# Powersupply.net
KiCad netlist of a schematic drawn in Altium Designer
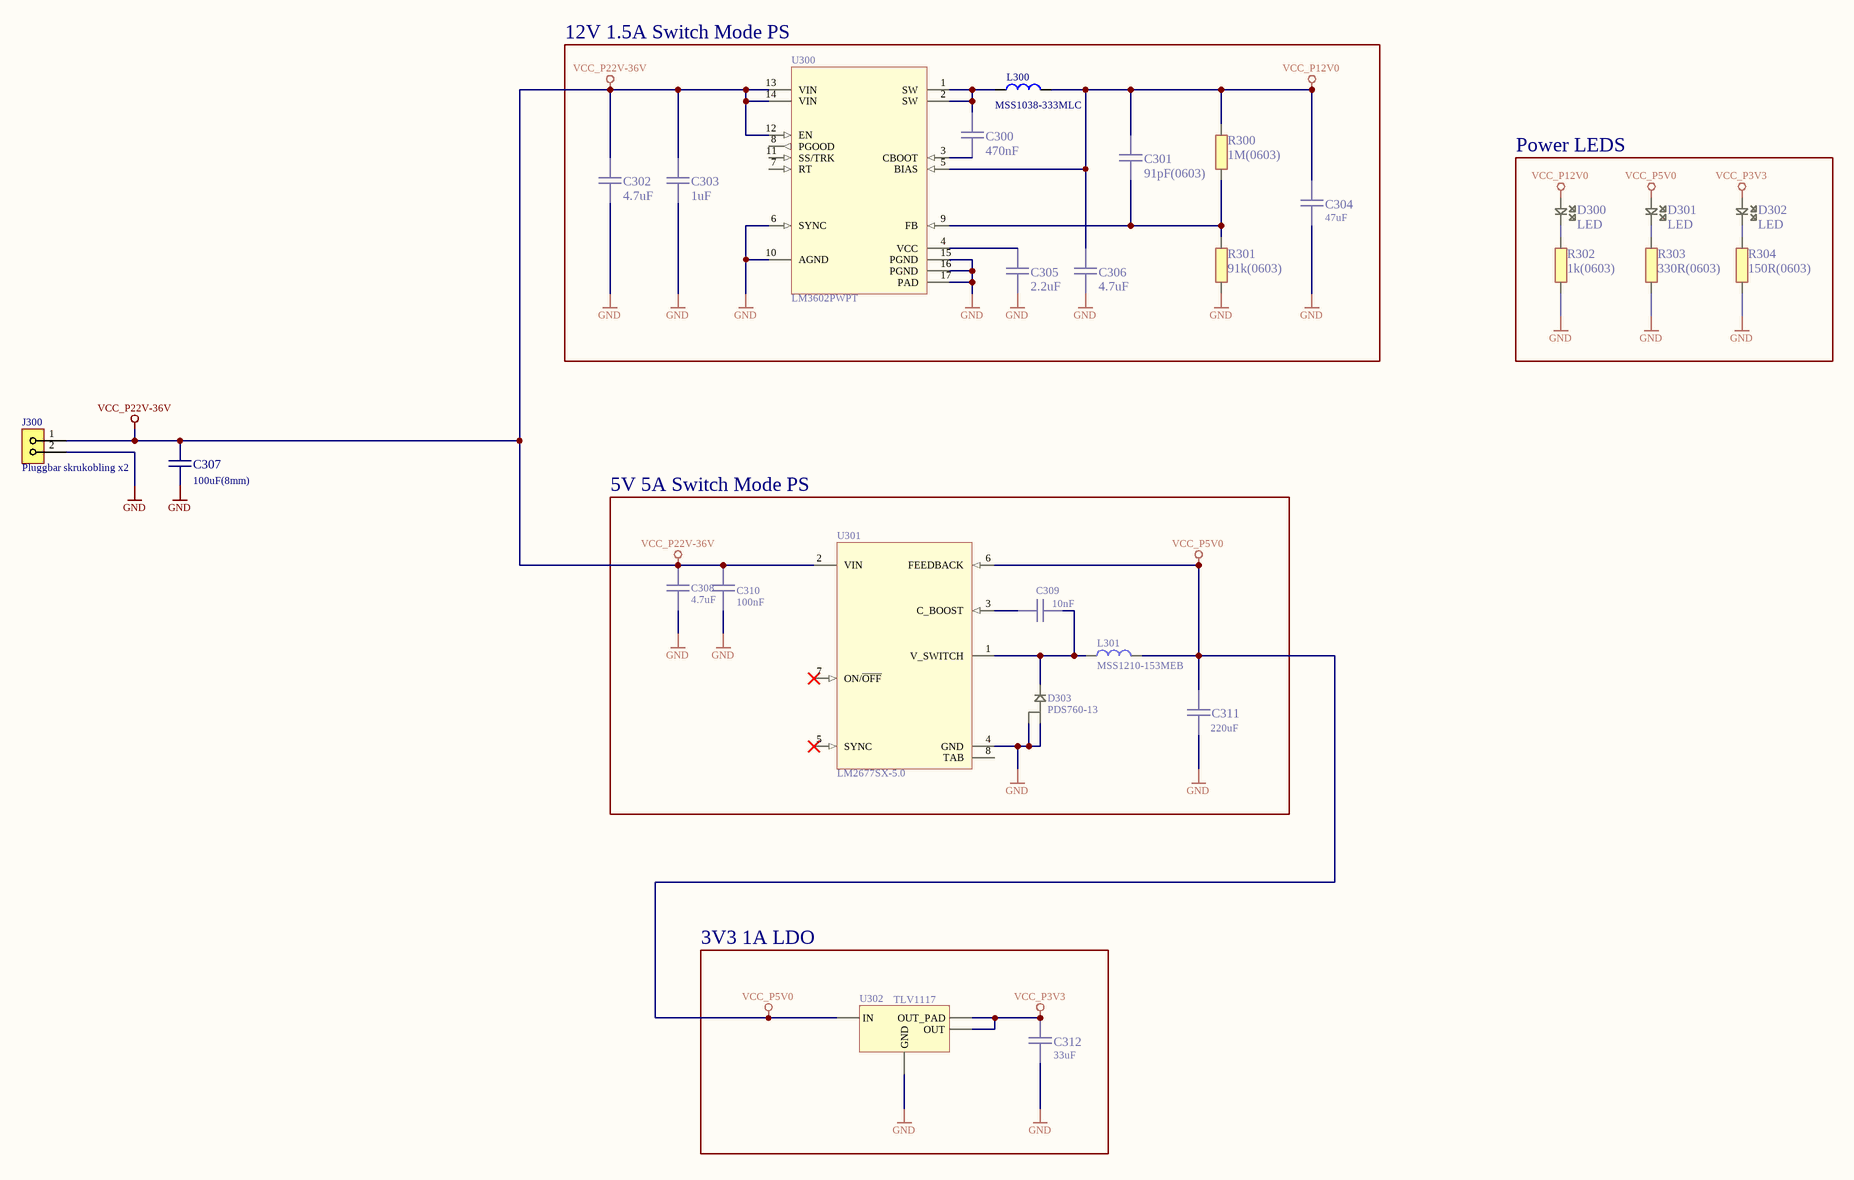
[diagram p0: Powersupply.SchDoc]

(export (version "E")
  (design (tool "Eeschema 10.0.6"))
  (components
    (comp (ref "C300")
      (value "470nF")
      (footprint "CAPC0805(2012)100_N")
      (description "470nF 0805 chip X7R 50V")
      (libsource (lib "OVLib") (part "CAP"))
    )
    (comp (ref "C301")
      (value "91pF(0603)")
      (footprint "CAPC0603(1608)55_N")
      (description "100nF 0603 5% NP0 50V")
      (libsource (lib "OVLib") (part "CAP"))
    )
    (comp (ref "C302")
      (value "4.7uF")
      (footprint "CAPC1206(3216)170_N")
      (description "100nF 1206 chip X7R 50V")
      (libsource (lib "OVLib") (part "CAP"))
    )
    (comp (ref "C303")
      (value "1uF")
      (footprint "CAPC1206(3216)170_N")
      (description "1uF 1206 chip X7R 50V")
      (libsource (lib "OVLib") (part "CAP"))
    )
    (comp (ref "C304")
      (value "T495D476M025ATE120")
      (footprint "CAPMP7342X30N")
      (fields (field (name "MANUFACTURER") "Kemet") (field (name "VERDI") "47uF"))
      (libsource (lib "T495D476M025ATE120") (part "T495D476M025ATE120"))
    )
    (comp (ref "C305")
      (value "2.2uF")
      (footprint "CAPC0603(1608)55_N")
      (description "2.2uF 0603 chip X7R 6.3V")
      (libsource (lib "OVLib") (part "CAP"))
    )
    (comp (ref "C306")
      (value "4.7uF")
      (footprint "CAPC1206(3216)170_N")
      (description "100nF 1206 chip X7R 50V")
      (libsource (lib "OVLib") (part "CAP"))
    )
    (comp (ref "C307")
      (value "100uF(8mm)")
      (footprint "CAPPR35D08H11")
      (description "D=8mm Radial, 20% 50V 3,5mm pitch")
      (libsource (lib "OVLib") (part "CAP"))
    )
    (comp (ref "C308")
      (value "4.7uF")
      (footprint "CAPC1206(3216)170_N")
      (description "100nF 1206 chip X7R 50V")
      (libsource (lib "OVLib") (part "CAP"))
    )
    (comp (ref "C309")
      (value "10nF")
      (footprint "CAPC0805(2012)100_N")
      (description "100nF 0805 chip X7R 50V")
      (libsource (lib "OVLib") (part "CAP"))
    )
    (comp (ref "C310")
      (value "100nF")
      (footprint "CAPC0805(2012)100_N")
      (description "100nF 0805 chip X7R 50V")
      (libsource (lib "OVLib") (part "CAP"))
    )
    (comp (ref "C311")
      (value "10TPB220ML")
      (footprint "CAPMP7342X30N")
      (fields (field (name "VERDI") "220uF"))
      (libsource (lib "10TPB220ML") (part "10TPB220ML"))
    )
    (comp (ref "C312")
      (value "10TPB33M")
      (footprint "CAPMP7342X30N")
      (fields (field (name "VERDI") "33uF"))
      (libsource (lib "10TPB33M") (part "10TPB33M"))
    )
    (comp (ref "D300")
      (value "LED")
      (footprint "I_LEDC0603(1608)_N")
      (description "SMD")
      (libsource (lib "OVLib") (part "LED"))
    )
    (comp (ref "D301")
      (value "LED")
      (footprint "I_LEDC0603(1608)_N")
      (description "SMD")
      (libsource (lib "OVLib") (part "LED"))
    )
    (comp (ref "D302")
      (value "LED")
      (footprint "I_LEDC0603(1608)_N")
      (description "SMD")
      (libsource (lib "OVLib") (part "LED"))
    )
    (comp (ref "D303")
      (value "PDS760-13")
      (footprint "DFN540P650X115-3N")
      (description "SCHOTTKY RECTIFIER POWERDI5")
      (libsource (lib "PDS760-13") (part "PDS760-13"))
    )
    (comp (ref "J300")
      (value "Pluggbar skrukobling x2")
      (footprint "FCI-20020110-C021A01LF")
      (description "Skruplint")
      (libsource (lib "OVLib") (part "Header1x2"))
    )
    (comp (ref "L300")
      (value "MSS1038-333MLC")
      (footprint "INDP102100X40N")
      (description "INDUCTOR, PWR, 33UH, 2.3A, 20%,13MHZ")
      (libsource (lib "MSS1038-333MLC") (part "MSS1038-333MLC"))
    )
    (comp (ref "L301")
      (value "MSS1210-153MEB")
      (footprint "INDP123123X100N")
      (description "INDUCTOR, PWR, 15UH, 8.7A, 20%,12MHZ")
      (libsource (lib "MSS1210-153MEB") (part "MSS1210-153MEB"))
    )
    (comp (ref "R300")
      (value "1M(0603)")
      (footprint "RESC0603(1608)_N")
      (description "0603 0.1W 1% Thick film resistor")
      (libsource (lib "OVLib") (part "Resistor2"))
    )
    (comp (ref "R301")
      (value "91k(0603)")
      (footprint "RESC0603(1608)_N")
      (description "91k 0603 0.1W 1% Thick film resistor")
      (libsource (lib "OVLib") (part "Resistor2"))
    )
    (comp (ref "R302")
      (value "1k(0603)")
      (footprint "RESC0603(1608)_N")
      (description "0603 0.1W 1% Thick film resistor")
      (libsource (lib "OVLib") (part "Resistor2"))
    )
    (comp (ref "R303")
      (value "330R(0603)")
      (footprint "RESC0603(1608)_N")
      (description "330R 0603 0.1W 1% Thick film resistor")
      (libsource (lib "OVLib") (part "Resistor2"))
    )
    (comp (ref "R304")
      (value "150R(0603)")
      (footprint "RESC0603(1608)_N")
      (description "0603 0.1W 1% Thick film resistor")
      (libsource (lib "OVLib") (part "Resistor2"))
    )
    (comp (ref "U300")
      (value "LM3602PWPT")
      (footprint "HTSSOP65P640X120_HS-17N")
      (fields (field (name "MPN") "LM43602PWPT") (field (name "MANUFACTURER") "Texas Instruments"))
      (libsource (lib "LM43602PWPT") (part "LM3602PWPT"))
    )
    (comp (ref "U301")
      (value "LM2677SX-5.0")
      (footprint "DPAK127P1336X457-8N")
      (libsource (lib "LM2677SX-5.0") (part "LM2677SX-5.0"))
    )
    (comp (ref "U302")
      (value "TLV1117")
      (footprint "SOT230P700X180-4N")
      (description "Low dropout regulator")
      (libsource (lib "OVLib") (part "LDO_REGULATOR"))
    )
  )
  (nets
    (net (code "1") (name "GND") (class "Default")
      (node (ref "C302") (pin "1") (pinfunction "1_1") (pintype "passive"))
      (node (ref "C303") (pin "1") (pinfunction "1_1") (pintype "passive"))
      (node (ref "C304") (pin "1") (pinfunction "1_1") (pintype "passive"))
      (node (ref "C305") (pin "1") (pinfunction "1_1") (pintype "passive"))
      (node (ref "C306") (pin "1") (pinfunction "1_1") (pintype "passive"))
      (node (ref "C307") (pin "1") (pinfunction "1_1") (pintype "passive"))
      (node (ref "C308") (pin "1") (pinfunction "1_1") (pintype "passive"))
      (node (ref "C310") (pin "1") (pinfunction "1_1") (pintype "passive"))
      (node (ref "C311") (pin "1") (pinfunction "1_1") (pintype "passive"))
      (node (ref "C312") (pin "1") (pinfunction "1_1") (pintype "passive"))
      (node (ref "D303") (pin "1") (pinfunction "A_1") (pintype "passive"))
      (node (ref "D303") (pin "2") (pinfunction "A_2") (pintype "passive"))
      (node (ref "J300") (pin "2") (pinfunction "2_2") (pintype "passive"))
      (node (ref "R301") (pin "1") (pinfunction "1_1") (pintype "passive"))
      (node (ref "R302") (pin "1") (pinfunction "1_1") (pintype "passive"))
      (node (ref "R303") (pin "1") (pinfunction "1_1") (pintype "passive"))
      (node (ref "R304") (pin "1") (pinfunction "1_1") (pintype "passive"))
      (node (ref "U300") (pin "10") (pinfunction "AGND_10") (pintype "power_in"))
      (node (ref "U300") (pin "15") (pinfunction "PGND_15") (pintype "power_in"))
      (node (ref "U300") (pin "16") (pinfunction "PGND_16") (pintype "power_in"))
      (node (ref "U300") (pin "17") (pinfunction "PAD_17") (pintype "power_in"))
      (node (ref "U300") (pin "6") (pinfunction "SYNC_6") (pintype "input"))
      (node (ref "U301") (pin "4") (pinfunction "GND_4") (pintype "power_in"))
      (node (ref "U302") (pin "1") (pinfunction "GND_1") (pintype "power_in"))
    )
    (net (code "2") (name "Net-(C300-Pad2)") (class "Default")
      (node (ref "C300") (pin "2") (pinfunction "2_2") (pintype "passive"))
      (node (ref "L300") (pin "1") (pinfunction "1_1") (pintype "passive"))
      (node (ref "U300") (pin "1") (pinfunction "SW_1") (pintype "power_in"))
      (node (ref "U300") (pin "2") (pinfunction "SW_2") (pintype "power_in"))
    )
    (net (code "3") (name "Net-(D300-Pad2)") (class "Default")
      (node (ref "D300") (pin "2") (pinfunction "2_2") (pintype "passive"))
      (node (ref "R302") (pin "2") (pinfunction "2_2") (pintype "passive"))
    )
    (net (code "4") (name "Net-(D301-Pad2)") (class "Default")
      (node (ref "D301") (pin "2") (pinfunction "2_2") (pintype "passive"))
      (node (ref "R303") (pin "2") (pinfunction "2_2") (pintype "passive"))
    )
    (net (code "5") (name "Net-(D302-Pad2)") (class "Default")
      (node (ref "D302") (pin "2") (pinfunction "2_2") (pintype "passive"))
      (node (ref "R304") (pin "2") (pinfunction "2_2") (pintype "passive"))
    )
    (net (code "6") (name "Net-(D303-K)") (class "Default")
      (node (ref "C309") (pin "2") (pinfunction "2_2") (pintype "passive"))
      (node (ref "D303") (pin "3") (pinfunction "K_3") (pintype "passive"))
      (node (ref "L301") (pin "1") (pinfunction "1_1") (pintype "passive"))
      (node (ref "U301") (pin "1") (pinfunction "V_SWITCH_1") (pintype "power_in"))
    )
    (net (code "7") (name "Net-(U300-CBOOT)") (class "Default")
      (node (ref "C300") (pin "1") (pinfunction "1_1") (pintype "passive"))
      (node (ref "U300") (pin "3") (pinfunction "CBOOT_3") (pintype "input"))
    )
    (net (code "8") (name "Net-(U300-FB)") (class "Default")
      (node (ref "C301") (pin "1") (pinfunction "1_1") (pintype "passive"))
      (node (ref "R300") (pin "1") (pinfunction "1_1") (pintype "passive"))
      (node (ref "R301") (pin "2") (pinfunction "2_2") (pintype "passive"))
      (node (ref "U300") (pin "9") (pinfunction "FB_9") (pintype "input"))
    )
    (net (code "9") (name "Net-(U300-VCC)") (class "Default")
      (node (ref "C305") (pin "2") (pinfunction "2_2") (pintype "passive"))
      (node (ref "U300") (pin "4") (pinfunction "VCC_4") (pintype "power_in"))
    )
    (net (code "10") (name "Net-(U301-C_BOOST)") (class "Default")
      (node (ref "C309") (pin "1") (pinfunction "1_1") (pintype "passive"))
      (node (ref "U301") (pin "3") (pinfunction "C_BOOST_3") (pintype "input"))
    )
    (net (code "11") (name "VCC_P3V3") (class "Default")
      (node (ref "C312") (pin "2") (pinfunction "2_2") (pintype "passive"))
      (node (ref "D302") (pin "1") (pinfunction "1_1") (pintype "passive"))
      (node (ref "U302") (pin "2") (pinfunction "OUT_PAD_2") (pintype "power_in"))
      (node (ref "U302") (pin "4") (pinfunction "OUT_4") (pintype "power_in"))
    )
    (net (code "12") (name "VCC_P5V0") (class "Default")
      (node (ref "C311") (pin "2") (pinfunction "2_2") (pintype "passive"))
      (node (ref "D301") (pin "1") (pinfunction "1_1") (pintype "passive"))
      (node (ref "L301") (pin "2") (pinfunction "2_2") (pintype "passive"))
      (node (ref "U301") (pin "6") (pinfunction "FEEDBACK_6") (pintype "input"))
      (node (ref "U302") (pin "3") (pinfunction "IN_3") (pintype "power_in"))
    )
    (net (code "13") (name "VCC_P12V0") (class "Default")
      (node (ref "C301") (pin "2") (pinfunction "2_2") (pintype "passive"))
      (node (ref "C304") (pin "2") (pinfunction "2_2") (pintype "passive"))
      (node (ref "C306") (pin "2") (pinfunction "2_2") (pintype "passive"))
      (node (ref "D300") (pin "1") (pinfunction "1_1") (pintype "passive"))
      (node (ref "L300") (pin "2") (pinfunction "2_2") (pintype "passive"))
      (node (ref "R300") (pin "2") (pinfunction "2_2") (pintype "passive"))
      (node (ref "U300") (pin "5") (pinfunction "BIAS_5") (pintype "input"))
    )
    (net (code "14") (name "VCC_P22V-36V") (class "Default")
      (node (ref "C302") (pin "2") (pinfunction "2_2") (pintype "passive"))
      (node (ref "C303") (pin "2") (pinfunction "2_2") (pintype "passive"))
      (node (ref "C307") (pin "2") (pinfunction "2_2") (pintype "passive"))
      (node (ref "C308") (pin "2") (pinfunction "2_2") (pintype "passive"))
      (node (ref "C310") (pin "2") (pinfunction "2_2") (pintype "passive"))
      (node (ref "J300") (pin "1") (pinfunction "1_1") (pintype "passive"))
      (node (ref "U300") (pin "12") (pinfunction "EN_12") (pintype "input"))
      (node (ref "U300") (pin "13") (pinfunction "VIN_13") (pintype "power_in"))
      (node (ref "U300") (pin "14") (pinfunction "VIN_14") (pintype "power_in"))
      (node (ref "U301") (pin "2") (pinfunction "VIN_2") (pintype "power_in"))
    )
    (net (code "15") (name "unconnected-(U300-PGOOD-Pad8)") (class "Default")
      (node (ref "U300") (pin "8") (pinfunction "PGOOD_8") (pintype "output"))
    )
    (net (code "16") (name "unconnected-(U300-RT-Pad7)") (class "Default")
      (node (ref "U300") (pin "7") (pinfunction "RT_7") (pintype "input"))
    )
    (net (code "17") (name "unconnected-(U300-SS{slash}TRK-Pad11)") (class "Default")
      (node (ref "U300") (pin "11") (pinfunction "SS/TRK_11") (pintype "input"))
    )
    (net (code "18") (name "unconnected-(U301-ON{slash}~{OFF}-Pad7)") (class "Default")
      (node (ref "U301") (pin "7") (pinfunction "ON/~{OFF}_7") (pintype "input+no_connect"))
    )
    (net (code "19") (name "unconnected-(U301-SYNC-Pad5)") (class "Default")
      (node (ref "U301") (pin "5") (pinfunction "SYNC_5") (pintype "input+no_connect"))
    )
    (net (code "20") (name "unconnected-(U301-TAB-Pad8)") (class "Default")
      (node (ref "U301") (pin "8") (pinfunction "TAB_8") (pintype "passive"))
    )
  )
)
